# SmartHome_V3.net
KiCad netlist of a schematic drawn in Altium Designer
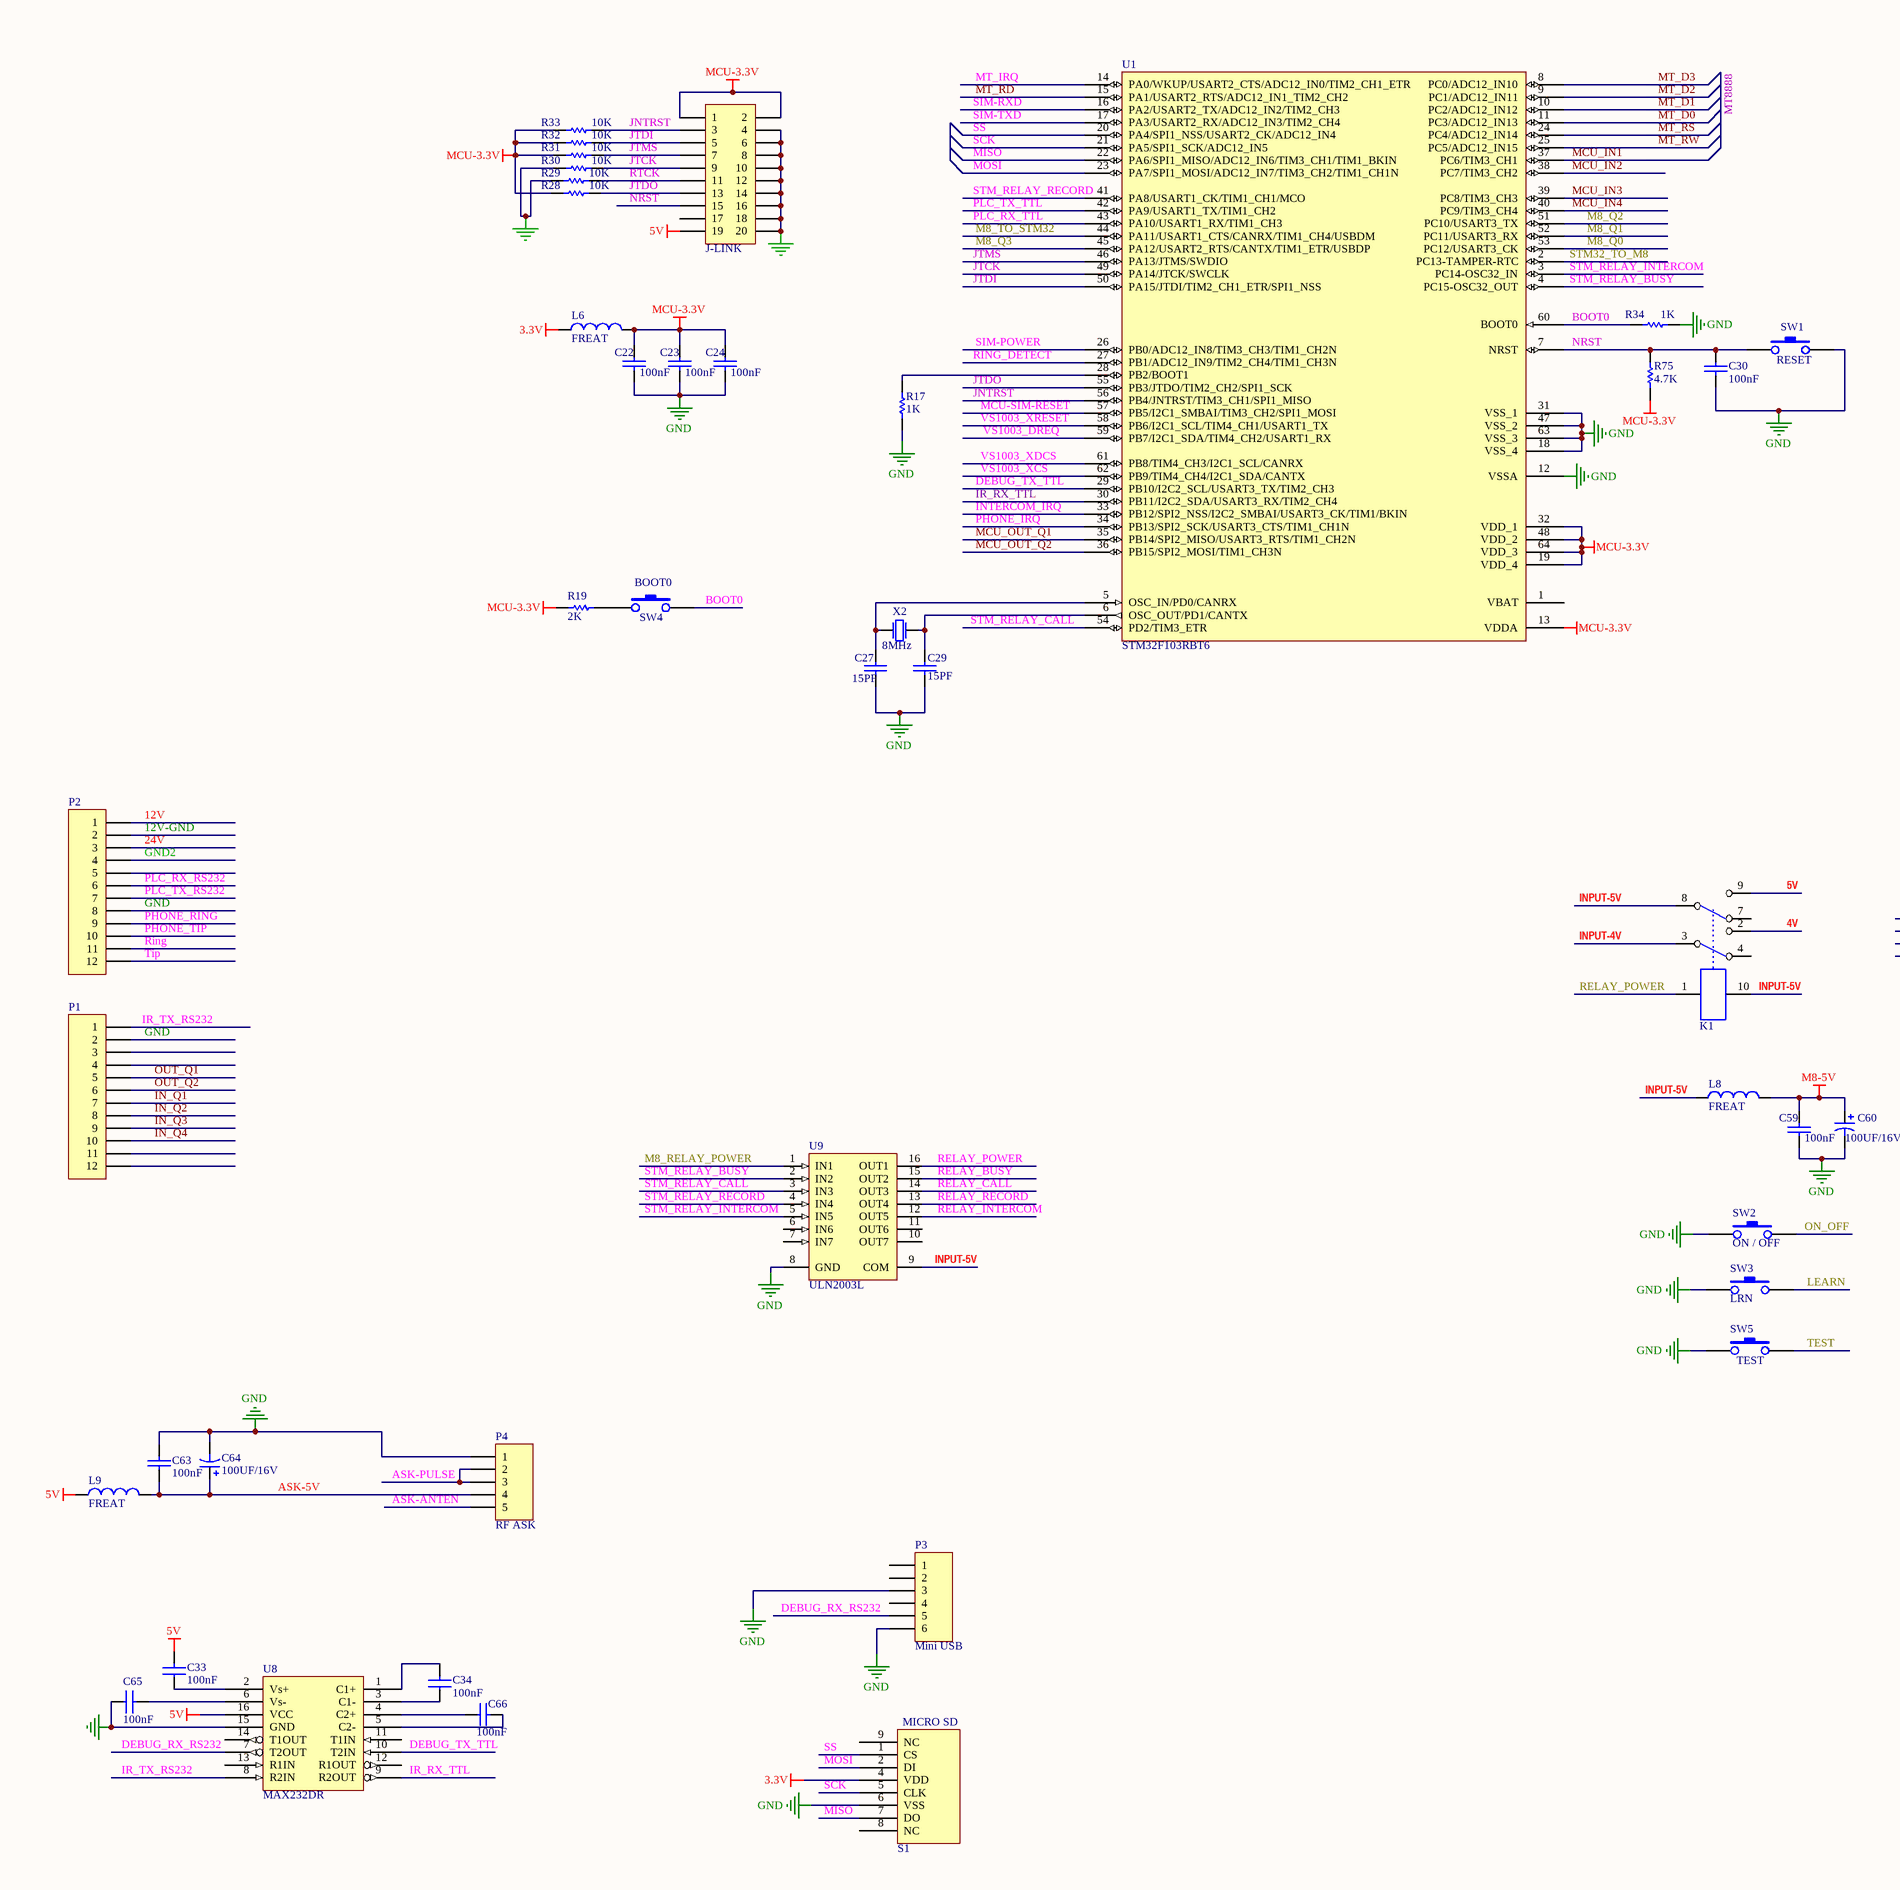
[diagram p0: SmartHome V3.SchDoc, left]
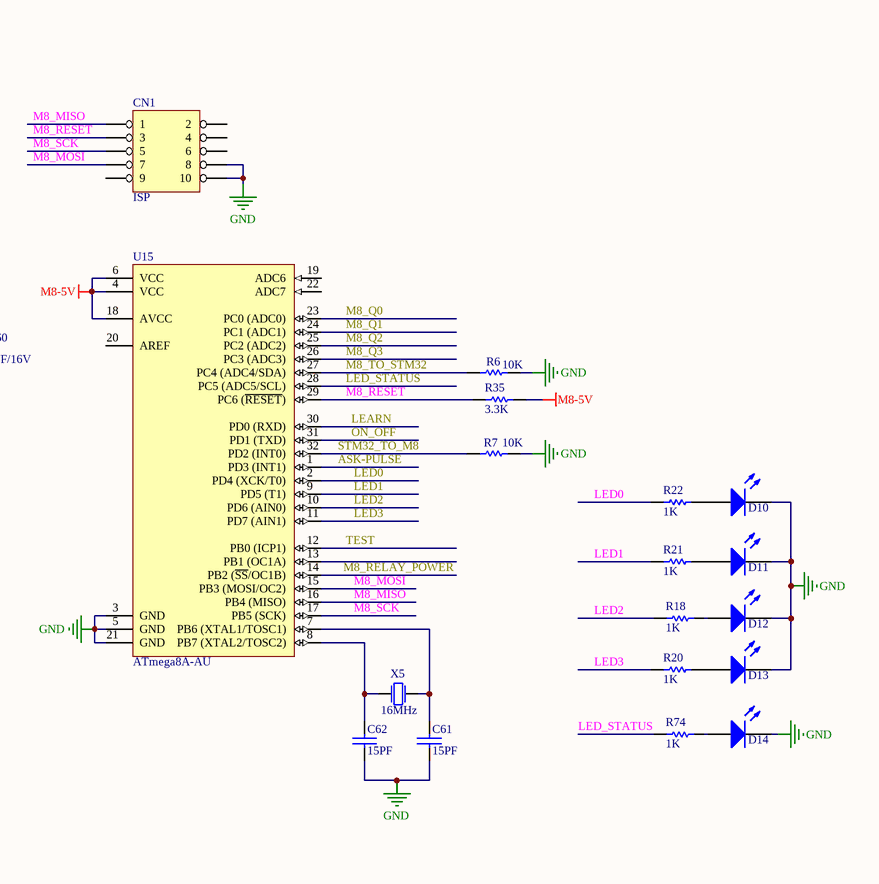
[diagram p1: SmartHome V3.SchDoc, right]

(export (version "E")
  (design (tool "Eeschema 10.0.6"))
  (components
    (comp (ref "C22") (value "100nF") (footprint "0805C") (libsource (lib "*") (part "CAP")))
    (comp (ref "C23") (value "100nF") (footprint "0805C") (libsource (lib "*") (part "CAP")))
    (comp (ref "C24") (value "100nF") (footprint "0805C") (libsource (lib "*") (part "CAP")))
    (comp (ref "C27")
      (value "15PF")
      (footprint "0805c")
      (description "Capacitor")
      (libsource (lib "") (part "CAP_1"))
    )
    (comp (ref "C29")
      (value "15PF")
      (footprint "0805c")
      (description "Capacitor")
      (libsource (lib "") (part "CAP_1"))
    )
    (comp (ref "C30")
      (value "100nF")
      (footprint "0805C")
      (description "Capacitor")
      (libsource (lib "") (part "CAP_1"))
    )
    (comp (ref "C33") (value "100nF") (footprint "0805C") (libsource (lib "*") (part "CAP NP")))
    (comp (ref "C34") (value "100nF") (footprint "0805c") (libsource (lib "*") (part "CAP NP")))
    (comp (ref "C59") (value "100nF") (footprint "0805C") (libsource (lib "*") (part "CAP")))
    (comp (ref "C60")
      (value "100UF/16V")
      (footprint "100UF-SMD")
      (description "Polarized Capacitor (Radial)")
      (fields (field (name "Comment") "100uF / 16V SMD"))
      (libsource (lib "Miscellaneous Devices") (part "Cap Pol1"))
    )
    (comp (ref "C61")
      (value "15PF")
      (footprint "0805c")
      (description "Capacitor")
      (libsource (lib "") (part "CAP_1"))
    )
    (comp (ref "C62")
      (value "15PF")
      (footprint "0805c")
      (description "Capacitor")
      (libsource (lib "") (part "CAP_1"))
    )
    (comp (ref "C63") (value "100nF") (footprint "0805C") (libsource (lib "*") (part "CAP")))
    (comp (ref "C64")
      (value "100UF/16V")
      (footprint "100UF-SMD")
      (description "Polarized Capacitor (Radial)")
      (fields (field (name "Comment") "100uF / 16V SMD"))
      (libsource (lib "") (part "Cap Pol1_1"))
    )
    (comp (ref "C65") (value "100nF") (footprint "0805c") (libsource (lib "*") (part "CAP NP")))
    (comp (ref "C66") (value "100nF") (footprint "0805c") (libsource (lib "*") (part "CAP NP")))
    (comp (ref "CN1") (value "ISP") (footprint "IDC2.54-V10D") (libsource (lib "*") (part "HEADER 5X2")))
    (comp (ref "D10")
      (value "LED")
      (footprint "0805D")
      (description "Typical BLUE SiC LED")
      (fields (field (name "PUBLISHER") "Altium Limited"))
      (libsource (lib "Miscellaneous Devices") (part "LED3"))
    )
    (comp (ref "D11")
      (value "LED")
      (footprint "0805D")
      (description "Typical BLUE SiC LED")
      (fields (field (name "PUBLISHER") "Altium Limited"))
      (libsource (lib "Miscellaneous Devices") (part "LED3"))
    )
    (comp (ref "D12")
      (value "LED")
      (footprint "0805D")
      (description "Typical BLUE SiC LED")
      (fields (field (name "PUBLISHER") "Altium Limited"))
      (libsource (lib "Miscellaneous Devices") (part "LED3"))
    )
    (comp (ref "D13")
      (value "LED")
      (footprint "0805D")
      (description "Typical BLUE SiC LED")
      (fields (field (name "PUBLISHER") "Altium Limited"))
      (libsource (lib "Miscellaneous Devices") (part "LED3"))
    )
    (comp (ref "D14")
      (value "LED")
      (footprint "0805D")
      (description "Typical BLUE SiC LED")
      (fields (field (name "PUBLISHER") "Altium Limited"))
      (libsource (lib "Miscellaneous Devices") (part "LED3"))
    )
    (comp (ref "J-LINK")
      (value "IDC 20")
      (footprint "IDC2.54-V20D")
      (description "Header, 10-Pin, Dual row")
      (fields (field (name "PUBLISHER") "Altium Limited"))
      (libsource (lib "*") (part "Header 10X2"))
    )
    (comp (ref "K1")
      (value "RELAY 5V")
      (footprint "RELAY G6H")
      (libsource (lib "*") (part "RELAY DPDT-G6HU"))
    )
    (comp (ref "L6")
      (value "FREAT")
      (footprint "1206")
      (description "Inductor")
      (fields (field (name "PUBLISHER") "Altium Limited"))
      (libsource (lib "Miscellaneous Devices") (part "Inductor"))
    )
    (comp (ref "L8")
      (value "FREAT")
      (footprint "1206")
      (description "Inductor")
      (fields (field (name "PUBLISHER") "Altium Limited"))
      (libsource (lib "Miscellaneous Devices") (part "Inductor"))
    )
    (comp (ref "L9")
      (value "FREAT")
      (footprint "1206")
      (description "Inductor")
      (fields (field (name "PUBLISHER") "Altium Limited"))
      (libsource (lib "") (part "Inductor_1"))
    )
    (comp (ref "P1")
      (value "FONIX-12")
      (footprint "Fonit_Conector")
      (description "Header, 12-Pin")
      (fields (field (name "PUBLISHER") "Altium Limited"))
      (libsource (lib "Miscellaneous Connectors") (part "Header 12"))
    )
    (comp (ref "P2")
      (value "FONIX-12")
      (footprint "Fonit_Conector")
      (description "Header, 12-Pin")
      (fields (field (name "PUBLISHER") "Altium Limited"))
      (libsource (lib "Miscellaneous Connectors") (part "Header 12"))
    )
    (comp (ref "P3")
      (value "Mini USB")
      (footprint "miniusb")
      (description "Header, 5-Pin")
      (fields (field (name "PUBLISHER") "DEBUGGER"))
      (libsource (lib "SmartHome V3") (part "Header 5"))
    )
    (comp (ref "P4")
      (value "RF ASK")
      (footprint "ASK-RF")
      (description "Header, 5-Pin")
      (fields (field (name "PUBLISHER") "Altium Limited"))
      (libsource (lib "Miscellaneous Connectors") (part "Header 5"))
    )
    (comp (ref "R6")
      (value "10K")
      (footprint "0805")
      (description "Semiconductor Resistor")
      (fields (field (name "PUBLISHER") "Altium Limited"))
      (libsource (lib "Miscellaneous Devices") (part "Res Semi"))
    )
    (comp (ref "R7")
      (value "10K")
      (footprint "0805")
      (description "Semiconductor Resistor")
      (fields (field (name "PUBLISHER") "Altium Limited"))
      (libsource (lib "Miscellaneous Devices") (part "Res Semi"))
    )
    (comp (ref "R17")
      (value "1K")
      (footprint "0805")
      (description "Semiconductor Resistor")
      (fields (field (name "Comment") "10K") (field (name "PUBLISHER") "Altium Limited"))
      (libsource (lib "Miscellaneous Devices") (part "Res Semi"))
    )
    (comp (ref "R18")
      (value "1K")
      (footprint "0805")
      (description "Resistor")
      (fields (field (name "PUBLISHER") "Altium Limited"))
      (libsource (lib "*") (part "Res1"))
    )
    (comp (ref "R19")
      (value "2K")
      (footprint "0805")
      (description "Semiconductor Resistor")
      (fields (field (name "Comment") "10K") (field (name "PUBLISHER") "Altium Limited"))
      (libsource (lib "Miscellaneous Devices") (part "Res Semi"))
    )
    (comp (ref "R20")
      (value "1K")
      (footprint "0805")
      (description "Resistor")
      (fields (field (name "PUBLISHER") "Altium Limited"))
      (libsource (lib "*") (part "Res1"))
    )
    (comp (ref "R21")
      (value "1K")
      (footprint "0805")
      (description "Resistor")
      (fields (field (name "PUBLISHER") "Altium Limited"))
      (libsource (lib "*") (part "Res1"))
    )
    (comp (ref "R22")
      (value "1K")
      (footprint "0805")
      (description "Resistor")
      (fields (field (name "PUBLISHER") "Altium Limited"))
      (libsource (lib "*") (part "Res1"))
    )
    (comp (ref "R28")
      (value "10K")
      (footprint "0805")
      (description "Resistor")
      (fields (field (name "PUBLISHER") "Altium Limited"))
      (libsource (lib "*") (part "Res1"))
    )
    (comp (ref "R29")
      (value "10K")
      (footprint "0805")
      (description "Resistor")
      (fields (field (name "PUBLISHER") "Altium Limited"))
      (libsource (lib "*") (part "Res1"))
    )
    (comp (ref "R30")
      (value "10K")
      (footprint "0805")
      (description "Resistor")
      (fields (field (name "PUBLISHER") "Altium Limited"))
      (libsource (lib "*") (part "Res1"))
    )
    (comp (ref "R31")
      (value "10K")
      (footprint "0805")
      (description "Resistor")
      (fields (field (name "PUBLISHER") "Altium Limited"))
      (libsource (lib "*") (part "Res1"))
    )
    (comp (ref "R32")
      (value "10K")
      (footprint "0805")
      (description "Resistor")
      (fields (field (name "PUBLISHER") "Altium Limited"))
      (libsource (lib "*") (part "Res1"))
    )
    (comp (ref "R33")
      (value "10K")
      (footprint "0805")
      (description "Resistor")
      (fields (field (name "PUBLISHER") "Altium Limited"))
      (libsource (lib "*") (part "Res1"))
    )
    (comp (ref "R34")
      (value "1K")
      (footprint "0805")
      (description "Semiconductor Resistor")
      (fields (field (name "PUBLISHER") "Altium Limited"))
      (libsource (lib "Miscellaneous Devices") (part "Res Semi"))
    )
    (comp (ref "R35")
      (value "3.3K")
      (footprint "0805")
      (description "Semiconductor Resistor")
      (fields (field (name "PUBLISHER") "Altium Limited"))
      (libsource (lib "Miscellaneous Devices") (part "Res Semi"))
    )
    (comp (ref "R74")
      (value "1K")
      (footprint "0805")
      (description "Resistor")
      (fields (field (name "PUBLISHER") "Altium Limited"))
      (libsource (lib "*") (part "Res1"))
    )
    (comp (ref "R75")
      (value "4.7K")
      (footprint "0805")
      (description "Semiconductor Resistor")
      (fields (field (name "PUBLISHER") "Altium Limited"))
      (libsource (lib "Miscellaneous Devices") (part "Res Semi"))
    )
    (comp (ref "S1")
      (value "MICRO SD")
      (footprint "MicroSD")
      (libsource (lib "Sheet1") (part "Component_1_1"))
    )
    (comp (ref "SW1")
      (value "SWITCH")
      (footprint "SWICH")
      (fields (field (name "ALTIUM_UNNAMED_2") "RESET"))
      (libsource (lib "*") (part "SW-PB"))
    )
    (comp (ref "SW2")
      (value "SWITCH")
      (footprint "SWICH")
      (fields (field (name "ALTIUM_UNNAMED_2") "ON / OFF"))
      (libsource (lib "*") (part "SW-PB"))
    )
    (comp (ref "SW3")
      (value "SWITCH")
      (footprint "SWICH")
      (fields (field (name "ALTIUM_UNNAMED_2") "LRN"))
      (libsource (lib "*") (part "SW-PB"))
    )
    (comp (ref "SW4")
      (value "SWITCH")
      (footprint "SWICH")
      (fields (field (name "ALTIUM_UNNAMED_1") "BOOT0"))
      (libsource (lib "*") (part "SW-PB"))
    )
    (comp (ref "SW5")
      (value "SWITCH")
      (footprint "SWICH")
      (fields (field (name "ALTIUM_UNNAMED_2") "TEST"))
      (libsource (lib "*") (part "SW-PB"))
    )
    (comp (ref "U1")
      (value "STM32F103RBT6")
      (footprint "LQFP64_L")
      (description "STM32 ARM-based 32-bit MCU with 128 Kbytes Flash, 64-pin LQFP, Industrial Temperature")
      (fields (field (name "PUBLISHER") "Altium Limited"))
      (libsource (lib "HomeAutomation") (part "STM32F103RBT6"))
    )
    (comp (ref "U8")
      (value "MAX232DR")
      (footprint "L16_N")
      (description "DUAL EIA-232 DRIVER/RECEIVER")
      (libsource (lib "*") (part "MAX232"))
    )
    (comp (ref "U9")
      (value "ULN2003L")
      (footprint "L16_N")
      (description "High-Voltage, High-Current Darlington Array")
      (fields (field (name "PUBLISHER") "Altium Limited"))
      (libsource (lib "Allegro Interface Darlington Driver") (part "ULN2003L"))
    )
    (comp (ref "U15")
      (value "ATmega8A-AU")
      (footprint "32A_N")
      (fields (field (name "PUBLISHER") "Altium Limited"))
      (libsource (lib "Atmel Microcontroller 8-Bit megaAVR") (part "ATmega8A-AU"))
    )
    (comp (ref "X2")
      (value "8MHz")
      (footprint "crystal")
      (description "Crystal Oscillator")
      (libsource (lib "*") (part "16.000MHZ"))
    )
    (comp (ref "X5")
      (value "16MHz")
      (footprint "crystal")
      (description "Crystal Oscillator")
      (libsource (lib "*") (part "16.000MHZ"))
    )
  )
  (nets
    (net (code "2") (name "/4V") (class "Default")
      (node (ref "K1") (pin "2") (pinfunction "NO1_2") (pintype "passive"))
    )
    (net (code "3") (name "/12V") (class "Default")
      (node (ref "P2") (pin "1") (pinfunction "1_1") (pintype "passive"))
    )
    (net (code "4") (name "/12V-GND") (class "Default")
      (node (ref "P2") (pin "2") (pinfunction "2_2") (pintype "passive"))
    )
    (net (code "5") (name "/24V") (class "Default")
      (node (ref "P2") (pin "3") (pinfunction "3_3") (pintype "passive"))
    )
    (net (code "6") (name "/ASK-5V") (class "Default")
      (node (ref "C63") (pin "1") (pintype "passive"))
      (node (ref "C64") (pin "1") (pinfunction "1_1") (pintype "passive"))
      (node (ref "L9") (pin "2") (pinfunction "2_2") (pintype "passive"))
      (node (ref "P4") (pin "4") (pinfunction "4_4") (pintype "passive"))
    )
    (net (code "7") (name "/ASK-ANTEN") (class "Default")
      (node (ref "P4") (pin "5") (pinfunction "5_5") (pintype "passive"))
    )
    (net (code "8") (name "/ASK-PULSE") (class "Default")
      (node (ref "P4") (pin "2") (pinfunction "2_2") (pintype "passive"))
      (node (ref "P4") (pin "3") (pinfunction "3_3") (pintype "passive"))
      (node (ref "U15") (pin "1") (pinfunction "PD3_(INT1)_1") (pintype "bidirectional"))
    )
    (net (code "9") (name "/BOOT0") (class "Default")
      (node (ref "R34") (pin "1") (pinfunction "1_1") (pintype "passive"))
      (node (ref "SW4") (pin "1") (pinfunction "1_1") (pintype "passive"))
      (node (ref "U1") (pin "60") (pinfunction "BOOT0_60") (pintype "input"))
    )
    (net (code "10") (name "/DEBUG_RX_RS232") (class "Default")
      (node (ref "P3") (pin "5") (pinfunction "5_5") (pintype "passive"))
      (node (ref "U8") (pin "7") (pinfunction "T2OUT_7") (pintype "output"))
    )
    (net (code "11") (name "/DEBUG_TX_TTL") (class "Default")
      (node (ref "U1") (pin "29") (pinfunction "PB10/I2C2_SCL/USART3_TX/TIM2_CH3_29") (pintype "bidirectional"))
      (node (ref "U8") (pin "10") (pinfunction "T2IN_10") (pintype "input"))
    )
    (net (code "12") (name "/GND2") (class "Default")
      (node (ref "P2") (pin "4") (pinfunction "4_4") (pintype "passive"))
    )
    (net (code "13") (name "/INPUT-4V") (class "Default")
      (node (ref "K1") (pin "3") (pinfunction "C1_3") (pintype "passive"))
    )
    (net (code "14") (name "/INPUT-5V") (class "Default")
      (node (ref "K1") (pin "10") (pinfunction "-_10") (pintype "passive"))
      (node (ref "K1") (pin "8") (pinfunction "C2_8") (pintype "passive"))
      (node (ref "L8") (pin "2") (pinfunction "2_2") (pintype "passive"))
      (node (ref "U9") (pin "9") (pinfunction "COM_9") (pintype "passive"))
    )
    (net (code "15") (name "/INTERCOM_IRQ") (class "Default")
      (node (ref "U1") (pin "33") (pinfunction "PB12/SPI2_NSS/I2C2_SMBAI/USART3_CK/TIM1/BKIN_33") (pintype "bidirectional"))
    )
    (net (code "16") (name "/IN_Q1") (class "Default")
      (node (ref "P1") (pin "7") (pinfunction "7_7") (pintype "passive"))
    )
    (net (code "17") (name "/IN_Q2") (class "Default")
      (node (ref "P1") (pin "8") (pinfunction "8_8") (pintype "passive"))
    )
    (net (code "18") (name "/IN_Q3") (class "Default")
      (node (ref "P1") (pin "9") (pinfunction "9_9") (pintype "passive"))
    )
    (net (code "19") (name "/IN_Q4") (class "Default")
      (node (ref "P1") (pin "10") (pinfunction "10_10") (pintype "passive"))
    )
    (net (code "20") (name "/IR_RX_TTL") (class "Default")
      (node (ref "U1") (pin "30") (pinfunction "PB11/I2C2_SDA/USART3_RX/TIM2_CH4_30") (pintype "bidirectional"))
      (node (ref "U8") (pin "9") (pinfunction "R2OUT_9") (pintype "output"))
    )
    (net (code "21") (name "/IR_TX_RS232") (class "Default")
      (node (ref "P1") (pin "1") (pinfunction "1_1") (pintype "passive"))
      (node (ref "U8") (pin "8") (pinfunction "R2IN_8") (pintype "input"))
    )
    (net (code "22") (name "/JNTRST") (class "Default")
      (node (ref "J-LINK") (pin "3") (pinfunction "3_3") (pintype "passive"))
      (node (ref "R33") (pin "1") (pinfunction "1_1") (pintype "passive"))
      (node (ref "U1") (pin "56") (pinfunction "PB4/JNTRST/TIM3_CH1/SPI1_MISO_56") (pintype "bidirectional"))
    )
    (net (code "23") (name "/JTCK") (class "Default")
      (node (ref "J-LINK") (pin "9") (pinfunction "9_9") (pintype "passive"))
      (node (ref "R30") (pin "1") (pinfunction "1_1") (pintype "passive"))
      (node (ref "U1") (pin "49") (pinfunction "PA14/JTCK/SWCLK_49") (pintype "bidirectional"))
    )
    (net (code "24") (name "/JTDI") (class "Default")
      (node (ref "J-LINK") (pin "5") (pinfunction "5_5") (pintype "passive"))
      (node (ref "R32") (pin "1") (pinfunction "1_1") (pintype "passive"))
      (node (ref "U1") (pin "50") (pinfunction "PA15/JTDI/TIM2_CH1_ETR/SPI1_NSS_50") (pintype "bidirectional"))
    )
    (net (code "25") (name "/JTDO") (class "Default")
      (node (ref "J-LINK") (pin "13") (pinfunction "13_13") (pintype "passive"))
      (node (ref "R28") (pin "1") (pinfunction "1_1") (pintype "passive"))
      (node (ref "U1") (pin "55") (pinfunction "PB3/JTDO/TIM2_CH2/SPI1_SCK_55") (pintype "bidirectional"))
    )
    (net (code "26") (name "/JTMS") (class "Default")
      (node (ref "J-LINK") (pin "7") (pinfunction "7_7") (pintype "passive"))
      (node (ref "R31") (pin "1") (pinfunction "1_1") (pintype "passive"))
      (node (ref "U1") (pin "46") (pinfunction "PA13/JTMS/SWDIO_46") (pintype "bidirectional"))
    )
    (net (code "27") (name "/LEARN") (class "Default")
      (node (ref "SW3") (pin "1") (pinfunction "1_1") (pintype "passive"))
      (node (ref "U15") (pin "30") (pinfunction "PD0_(RXD)_30") (pintype "bidirectional"))
    )
    (net (code "28") (name "/LED0") (class "Default")
      (node (ref "R22") (pin "1") (pinfunction "1_1") (pintype "passive"))
      (node (ref "U15") (pin "2") (pinfunction "PD4_(XCK/T0)_2") (pintype "bidirectional"))
    )
    (net (code "29") (name "/LED1") (class "Default")
      (node (ref "R21") (pin "1") (pinfunction "1_1") (pintype "passive"))
      (node (ref "U15") (pin "9") (pinfunction "PD5_(T1)_9") (pintype "bidirectional"))
    )
    (net (code "30") (name "/LED2") (class "Default")
      (node (ref "R18") (pin "1") (pinfunction "1_1") (pintype "passive"))
      (node (ref "U15") (pin "10") (pinfunction "PD6_(AIN0)_10") (pintype "bidirectional"))
    )
    (net (code "31") (name "/LED3") (class "Default")
      (node (ref "R20") (pin "1") (pinfunction "1_1") (pintype "passive"))
      (node (ref "U15") (pin "11") (pinfunction "PD7_(AIN1)_11") (pintype "bidirectional"))
    )
    (net (code "32") (name "/LED_STATUS") (class "Default")
      (node (ref "R74") (pin "1") (pinfunction "1_1") (pintype "passive"))
      (node (ref "U15") (pin "28") (pinfunction "PC5_(ADC5/SCL)_28") (pintype "bidirectional"))
    )
    (net (code "33") (name "/M8_MISO") (class "Default")
      (node (ref "CN1") (pin "1") (pinfunction "1_1") (pintype "passive"))
      (node (ref "U15") (pin "16") (pinfunction "PB4_(MISO)_16") (pintype "bidirectional"))
    )
    (net (code "34") (name "/M8_MOSI") (class "Default")
      (node (ref "CN1") (pin "7") (pinfunction "7_7") (pintype "passive"))
      (node (ref "U15") (pin "15") (pinfunction "PB3_(MOSI/OC2)_15") (pintype "bidirectional"))
    )
    (net (code "35") (name "/M8_Q0") (class "Default")
      (node (ref "U1") (pin "53") (pinfunction "PC12/USART3_CK_53") (pintype "bidirectional"))
      (node (ref "U15") (pin "23") (pinfunction "PC0_(ADC0)_23") (pintype "bidirectional"))
    )
    (net (code "36") (name "/M8_Q1") (class "Default")
      (node (ref "U1") (pin "52") (pinfunction "PC11/USART3_RX_52") (pintype "bidirectional"))
      (node (ref "U15") (pin "24") (pinfunction "PC1_(ADC1)_24") (pintype "bidirectional"))
    )
    (net (code "37") (name "/M8_Q2") (class "Default")
      (node (ref "U1") (pin "51") (pinfunction "PC10/USART3_TX_51") (pintype "bidirectional"))
      (node (ref "U15") (pin "25") (pinfunction "PC2_(ADC2)_25") (pintype "bidirectional"))
    )
    (net (code "38") (name "/M8_Q3") (class "Default")
      (node (ref "U1") (pin "45") (pinfunction "PA12/USART2_RTS/CANTX/TIM1_ETR/USBDP_45") (pintype "bidirectional"))
      (node (ref "U15") (pin "26") (pinfunction "PC3_(ADC3)_26") (pintype "bidirectional"))
    )
    (net (code "39") (name "/M8_RELAY_POWER") (class "Default")
      (node (ref "U15") (pin "14") (pinfunction "PB2_(~{SS}/OC1B)_14") (pintype "bidirectional"))
      (node (ref "U9") (pin "1") (pinfunction "IN1_1") (pintype "input"))
    )
    (net (code "40") (name "/M8_RESET") (class "Default")
      (node (ref "CN1") (pin "3") (pinfunction "3_3") (pintype "passive"))
      (node (ref "R35") (pin "1") (pinfunction "1_1") (pintype "passive"))
      (node (ref "U15") (pin "29") (pinfunction "PC6_(~{RESET})_29") (pintype "bidirectional"))
    )
    (net (code "41") (name "/M8_SCK") (class "Default")
      (node (ref "CN1") (pin "5") (pinfunction "5_5") (pintype "passive"))
      (node (ref "U15") (pin "17") (pinfunction "PB5_(SCK)_17") (pintype "bidirectional"))
    )
    (net (code "42") (name "/M8_TO_STM32") (class "Default")
      (node (ref "R6") (pin "1") (pinfunction "1_1") (pintype "passive"))
      (node (ref "U1") (pin "44") (pinfunction "PA11/USART1_CTS/CANRX/TIM1_CH4/USBDM_44") (pintype "bidirectional"))
      (node (ref "U15") (pin "27") (pinfunction "PC4_(ADC4/SDA)_27") (pintype "bidirectional"))
    )
    (net (code "43") (name "/MCU-SIM-RESET") (class "Default")
      (node (ref "U1") (pin "57") (pinfunction "PB5/I2C1_SMBAI/TIM3_CH2/SPI1_MOSI_57") (pintype "bidirectional"))
    )
    (net (code "44") (name "/MCU_IN1") (class "Default")
      (node (ref "U1") (pin "37") (pinfunction "PC6/TIM3_CH1_37") (pintype "bidirectional"))
    )
    (net (code "45") (name "/MCU_IN2") (class "Default")
      (node (ref "U1") (pin "38") (pinfunction "PC7/TIM3_CH2_38") (pintype "bidirectional"))
    )
    (net (code "46") (name "/MCU_IN3") (class "Default")
      (node (ref "U1") (pin "39") (pinfunction "PC8/TIM3_CH3_39") (pintype "bidirectional"))
    )
    (net (code "47") (name "/MCU_IN4") (class "Default")
      (node (ref "U1") (pin "40") (pinfunction "PC9/TIM3_CH4_40") (pintype "bidirectional"))
    )
    (net (code "48") (name "/MCU_OUT_Q1") (class "Default")
      (node (ref "U1") (pin "35") (pinfunction "PB14/SPI2_MISO/USART3_RTS/TIM1_CH2N_35") (pintype "bidirectional"))
    )
    (net (code "49") (name "/MCU_OUT_Q2") (class "Default")
      (node (ref "U1") (pin "36") (pinfunction "PB15/SPI2_MOSI/TIM1_CH3N_36") (pintype "bidirectional"))
    )
    (net (code "50") (name "/MISO") (class "Default")
      (node (ref "S1") (pin "7") (pinfunction "DO_7") (pintype "passive"))
      (node (ref "U1") (pin "22") (pinfunction "PA6/SPI1_MISO/ADC12_IN6/TIM3_CH1/TIM1_BKIN_22") (pintype "bidirectional"))
    )
    (net (code "51") (name "/MOSI") (class "Default")
      (node (ref "S1") (pin "2") (pinfunction "DI_2") (pintype "passive"))
      (node (ref "U1") (pin "23") (pinfunction "PA7/SPI1_MOSI/ADC12_IN7/TIM3_CH2/TIM1_CH1N_23") (pintype "bidirectional"))
    )
    (net (code "52") (name "/MT_D0") (class "Default")
      (node (ref "U1") (pin "11") (pinfunction "PC3/ADC12_IN13_11") (pintype "bidirectional"))
    )
    (net (code "53") (name "/MT_D1") (class "Default")
      (node (ref "U1") (pin "10") (pinfunction "PC2/ADC12_IN12_10") (pintype "bidirectional"))
    )
    (net (code "54") (name "/MT_D2") (class "Default")
      (node (ref "U1") (pin "9") (pinfunction "PC1/ADC12_IN11_9") (pintype "bidirectional"))
    )
    (net (code "55") (name "/MT_D3") (class "Default")
      (node (ref "U1") (pin "8") (pinfunction "PC0/ADC12_IN10_8") (pintype "bidirectional"))
    )
    (net (code "56") (name "/MT_IRQ") (class "Default")
      (node (ref "U1") (pin "14") (pinfunction "PA0/WKUP/USART2_CTS/ADC12_IN0/TIM2_CH1_ETR_14") (pintype "bidirectional"))
    )
    (net (code "57") (name "/MT_RD") (class "Default")
      (node (ref "U1") (pin "15") (pinfunction "PA1/USART2_RTS/ADC12_IN1_TIM2_CH2_15") (pintype "bidirectional"))
    )
    (net (code "58") (name "/MT_RS") (class "Default")
      (node (ref "U1") (pin "24") (pinfunction "PC4/ADC12_IN14_24") (pintype "bidirectional"))
    )
    (net (code "59") (name "/MT_RW") (class "Default")
      (node (ref "U1") (pin "25") (pinfunction "PC5/ADC12_IN15_25") (pintype "bidirectional"))
    )
    (net (code "60") (name "/NRST") (class "Default")
      (node (ref "C30") (pin "1") (pinfunction "1_1") (pintype "passive"))
      (node (ref "J-LINK") (pin "15") (pinfunction "15_15") (pintype "passive"))
      (node (ref "R75") (pin "1") (pinfunction "1_1") (pintype "passive"))
      (node (ref "SW1") (pin "1") (pinfunction "1_1") (pintype "passive"))
      (node (ref "U1") (pin "7") (pinfunction "NRST_7") (pintype "bidirectional"))
    )
    (net (code "61") (name "/ON_OFF") (class "Default")
      (node (ref "SW2") (pin "1") (pinfunction "1_1") (pintype "passive"))
      (node (ref "U15") (pin "31") (pinfunction "PD1_(TXD)_31") (pintype "bidirectional"))
    )
    (net (code "62") (name "/OUT_Q1") (class "Default")
      (node (ref "P1") (pin "5") (pinfunction "5_5") (pintype "passive"))
    )
    (net (code "63") (name "/OUT_Q2") (class "Default")
      (node (ref "P1") (pin "6") (pinfunction "6_6") (pintype "passive"))
    )
    (net (code "64") (name "/PHONE_IRQ") (class "Default")
      (node (ref "U1") (pin "34") (pinfunction "PB13/SPI2_SCK/USART3_CTS/TIM1_CH1N_34") (pintype "bidirectional"))
    )
    (net (code "65") (name "/PHONE_RING") (class "Default")
      (node (ref "P2") (pin "9") (pinfunction "9_9") (pintype "passive"))
    )
    (net (code "66") (name "/PHONE_TIP") (class "Default")
      (node (ref "P2") (pin "10") (pinfunction "10_10") (pintype "passive"))
    )
    (net (code "67") (name "/PLC_RX_RS232") (class "Default")
      (node (ref "P2") (pin "6") (pinfunction "6_6") (pintype "passive"))
    )
    (net (code "68") (name "/PLC_RX_TTL") (class "Default")
      (node (ref "U1") (pin "43") (pinfunction "PA10/USART1_RX/TIM1_CH3_43") (pintype "bidirectional"))
    )
    (net (code "69") (name "/PLC_TX_RS232") (class "Default")
      (node (ref "P2") (pin "7") (pinfunction "7_7") (pintype "passive"))
    )
    (net (code "70") (name "/PLC_TX_TTL") (class "Default")
      (node (ref "U1") (pin "42") (pinfunction "PA9/USART1_TX/TIM1_CH2_42") (pintype "bidirectional"))
    )
    (net (code "71") (name "/RELAY_BUSY") (class "Default")
      (node (ref "U9") (pin "15") (pinfunction "OUT2_15") (pintype "open_collector"))
    )
    (net (code "72") (name "/RELAY_CALL") (class "Default")
      (node (ref "U9") (pin "14") (pinfunction "OUT3_14") (pintype "open_collector"))
    )
    (net (code "73") (name "/RELAY_INTERCOM") (class "Default")
      (node (ref "U9") (pin "12") (pinfunction "OUT5_12") (pintype "open_collector"))
    )
    (net (code "74") (name "/RELAY_POWER") (class "Default")
      (node (ref "K1") (pin "1") (pinfunction "+_1") (pintype "passive"))
      (node (ref "U9") (pin "16") (pinfunction "OUT1_16") (pintype "open_collector"))
    )
    (net (code "75") (name "/RELAY_RECORD") (class "Default")
      (node (ref "U9") (pin "13") (pinfunction "OUT4_13") (pintype "open_collector"))
    )
    (net (code "76") (name "/RING_DETECT") (class "Default")
      (node (ref "U1") (pin "27") (pinfunction "PB1/ADC12_IN9/TIM2_CH4/TIM1_CH3N_27") (pintype "bidirectional"))
    )
    (net (code "77") (name "/RTCK") (class "Default")
      (node (ref "J-LINK") (pin "11") (pinfunction "11_11") (pintype "passive"))
      (node (ref "R29") (pin "1") (pinfunction "1_1") (pintype "passive"))
    )
    (net (code "78") (name "/Ring") (class "Default")
      (node (ref "P2") (pin "11") (pinfunction "11_11") (pintype "passive"))
    )
    (net (code "79") (name "/SCK") (class "Default")
      (node (ref "S1") (pin "5") (pinfunction "CLK_5") (pintype "passive"))
      (node (ref "U1") (pin "21") (pinfunction "PA5/SPI1_SCK/ADC12_IN5_21") (pintype "bidirectional"))
    )
    (net (code "80") (name "/SIM-POWER") (class "Default")
      (node (ref "U1") (pin "26") (pinfunction "PB0/ADC12_IN8/TIM3_CH3/TIM1_CH2N_26") (pintype "bidirectional"))
    )
    (net (code "81") (name "/SIM-RXD") (class "Default")
      (node (ref "U1") (pin "16") (pinfunction "PA2/USART2_TX/ADC12_IN2/TIM2_CH3_16") (pintype "bidirectional"))
    )
    (net (code "82") (name "/SIM-TXD") (class "Default")
      (node (ref "U1") (pin "17") (pinfunction "PA3/USART2_RX/ADC12_IN3/TIM2_CH4_17") (pintype "bidirectional"))
    )
    (net (code "83") (name "/SS") (class "Default")
      (node (ref "S1") (pin "1") (pinfunction "CS_1") (pintype "passive"))
      (node (ref "U1") (pin "20") (pinfunction "PA4/SPI1_NSS/USART2_CK/ADC12_IN4_20") (pintype "bidirectional"))
    )
    (net (code "84") (name "/STM32_TO_M8") (class "Default")
      (node (ref "R7") (pin "1") (pinfunction "1_1") (pintype "passive"))
      (node (ref "U1") (pin "2") (pinfunction "PC13-TAMPER-RTC_2") (pintype "bidirectional"))
      (node (ref "U15") (pin "32") (pinfunction "PD2_(INT0)_32") (pintype "bidirectional"))
    )
    (net (code "85") (name "/STM_RELAY_BUSY") (class "Default")
      (node (ref "U1") (pin "4") (pinfunction "PC15-OSC32_OUT_4") (pintype "bidirectional"))
      (node (ref "U9") (pin "2") (pinfunction "IN2_2") (pintype "input"))
    )
    (net (code "86") (name "/STM_RELAY_CALL") (class "Default")
      (node (ref "U1") (pin "54") (pinfunction "PD2/TIM3_ETR_54") (pintype "bidirectional"))
      (node (ref "U9") (pin "3") (pinfunction "IN3_3") (pintype "input"))
    )
    (net (code "87") (name "/STM_RELAY_INTERCOM") (class "Default")
      (node (ref "U1") (pin "3") (pinfunction "PC14-OSC32_IN_3") (pintype "bidirectional"))
      (node (ref "U9") (pin "5") (pinfunction "IN5_5") (pintype "input"))
    )
    (net (code "88") (name "/STM_RELAY_RECORD") (class "Default")
      (node (ref "U1") (pin "41") (pinfunction "PA8/USART1_CK/TIM1_CH1/MCO_41") (pintype "bidirectional"))
      (node (ref "U9") (pin "4") (pinfunction "IN4_4") (pintype "input"))
    )
    (net (code "89") (name "/TEST") (class "Default")
      (node (ref "SW5") (pin "1") (pinfunction "1_1") (pintype "passive"))
      (node (ref "U15") (pin "12") (pinfunction "PB0_(ICP1)_12") (pintype "bidirectional"))
    )
    (net (code "90") (name "/Tip") (class "Default")
      (node (ref "P2") (pin "12") (pinfunction "12_12") (pintype "passive"))
    )
    (net (code "91") (name "/VS1003_DREQ") (class "Default")
      (node (ref "U1") (pin "59") (pinfunction "PB7/I2C1_SDA/TIM4_CH2/USART1_RX_59") (pintype "bidirectional"))
    )
    (net (code "92") (name "/VS1003_XCS") (class "Default")
      (node (ref "U1") (pin "62") (pinfunction "PB9/TIM4_CH4/I2C1_SDA/CANTX_62") (pintype "bidirectional"))
    )
    (net (code "93") (name "/VS1003_XDCS") (class "Default")
      (node (ref "U1") (pin "61") (pinfunction "PB8/TIM4_CH3/I2C1_SCL/CANRX_61") (pintype "bidirectional"))
    )
    (net (code "94") (name "/VS1003_XRESET") (class "Default")
      (node (ref "U1") (pin "58") (pinfunction "PB6/I2C1_SCL/TIM4_CH1/USART1_TX_58") (pintype "bidirectional"))
    )
    (net (code "96") (name "3.3V") (class "Default")
      (node (ref "L6") (pin "2") (pinfunction "2_2") (pintype "passive"))
      (node (ref "S1") (pin "4") (pinfunction "VDD_4") (pintype "passive"))
    )
    (net (code "97") (name "5V") (class "Default")
      (node (ref "C33") (pin "2") (pinfunction "2_2") (pintype "passive"))
      (node (ref "J-LINK") (pin "19") (pinfunction "19_19") (pintype "passive"))
      (node (ref "K1") (pin "9") (pinfunction "NO2_9") (pintype "passive"))
      (node (ref "L9") (pin "1") (pinfunction "1_1") (pintype "passive"))
      (node (ref "U8") (pin "16") (pinfunction "VCC_16") (pintype "power_in"))
    )
    (net (code "98") (name "GND") (class "Default")
      (node (ref "C22") (pin "2") (pintype "passive"))
      (node (ref "C23") (pin "2") (pintype "passive"))
      (node (ref "C24") (pin "2") (pintype "passive"))
      (node (ref "C27") (pin "2") (pinfunction "2_2") (pintype "passive"))
      (node (ref "C29") (pin "2") (pinfunction "2_2") (pintype "passive"))
      (node (ref "C30") (pin "2") (pinfunction "2_2") (pintype "passive"))
      (node (ref "C59") (pin "2") (pintype "passive"))
      (node (ref "C60") (pin "2") (pinfunction "2_2") (pintype "passive"))
      (node (ref "C61") (pin "2") (pinfunction "2_2") (pintype "passive"))
      (node (ref "C62") (pin "2") (pinfunction "2_2") (pintype "passive"))
      (node (ref "C63") (pin "2") (pintype "passive"))
      (node (ref "C64") (pin "2") (pinfunction "2_2") (pintype "passive"))
      (node (ref "C65") (pin "1") (pinfunction "1_1") (pintype "passive"))
      (node (ref "CN1") (pin "10") (pinfunction "10_10") (pintype "passive"))
      (node (ref "CN1") (pin "8") (pinfunction "8_8") (pintype "passive"))
      (node (ref "D10") (pin "2") (pinfunction "K_2") (pintype "passive"))
      (node (ref "D11") (pin "2") (pinfunction "K_2") (pintype "passive"))
      (node (ref "D12") (pin "2") (pinfunction "K_2") (pintype "passive"))
      (node (ref "D13") (pin "2") (pinfunction "K_2") (pintype "passive"))
      (node (ref "D14") (pin "2") (pinfunction "K_2") (pintype "passive"))
      (node (ref "J-LINK") (pin "10") (pinfunction "10_10") (pintype "passive"))
      (node (ref "J-LINK") (pin "12") (pinfunction "12_12") (pintype "passive"))
      (node (ref "J-LINK") (pin "14") (pinfunction "14_14") (pintype "passive"))
      (node (ref "J-LINK") (pin "16") (pinfunction "16_16") (pintype "passive"))
      (node (ref "J-LINK") (pin "18") (pinfunction "18_18") (pintype "passive"))
      (node (ref "J-LINK") (pin "20") (pinfunction "20_20") (pintype "passive"))
      (node (ref "J-LINK") (pin "4") (pinfunction "4_4") (pintype "passive"))
      (node (ref "J-LINK") (pin "6") (pinfunction "6_6") (pintype "passive"))
      (node (ref "J-LINK") (pin "8") (pinfunction "8_8") (pintype "passive"))
      (node (ref "P1") (pin "2") (pinfunction "2_2") (pintype "passive"))
      (node (ref "P2") (pin "8") (pinfunction "8_8") (pintype "passive"))
      (node (ref "P3") (pin "3") (pinfunction "3_3") (pintype "passive"))
      (node (ref "P3") (pin "6") (pinfunction "6_6") (pintype "passive"))
      (node (ref "P4") (pin "1") (pinfunction "1_1") (pintype "passive"))
      (node (ref "R17") (pin "1") (pinfunction "1_1") (pintype "passive"))
      (node (ref "R29") (pin "2") (pinfunction "2_2") (pintype "passive"))
      (node (ref "R30") (pin "2") (pinfunction "2_2") (pintype "passive"))
      (node (ref "R34") (pin "2") (pinfunction "2_2") (pintype "passive"))
      (node (ref "R6") (pin "2") (pinfunction "2_2") (pintype "passive"))
      (node (ref "R7") (pin "2") (pinfunction "2_2") (pintype "passive"))
      (node (ref "S1") (pin "6") (pinfunction "VSS_6") (pintype "passive"))
      (node (ref "SW1") (pin "2") (pinfunction "2_2") (pintype "passive"))
      (node (ref "SW2") (pin "2") (pinfunction "2_2") (pintype "passive"))
      (node (ref "SW3") (pin "2") (pinfunction "2_2") (pintype "passive"))
      (node (ref "SW5") (pin "2") (pinfunction "2_2") (pintype "passive"))
      (node (ref "U1") (pin "12") (pinfunction "VSSA_12") (pintype "power_in"))
      (node (ref "U1") (pin "18") (pinfunction "VSS_4_18") (pintype "power_in"))
      (node (ref "U1") (pin "31") (pinfunction "VSS_1_31") (pintype "power_in"))
      (node (ref "U1") (pin "47") (pinfunction "VSS_2_47") (pintype "power_in"))
      (node (ref "U1") (pin "63") (pinfunction "VSS_3_63") (pintype "power_in"))
      (node (ref "U15") (pin "21") (pinfunction "GND_21") (pintype "power_in"))
      (node (ref "U15") (pin "3") (pinfunction "GND_3") (pintype "power_in"))
      (node (ref "U15") (pin "5") (pinfunction "GND_5") (pintype "power_in"))
      (node (ref "U8") (pin "15") (pinfunction "GND_15") (pintype "power_in"))
      (node (ref "U9") (pin "8") (pinfunction "GND_8") (pintype "power_in"))
    )
    (net (code "99") (name "M8-5V") (class "Default")
      (node (ref "C59") (pin "1") (pintype "passive"))
      (node (ref "C60") (pin "1") (pinfunction "1_1") (pintype "passive"))
      (node (ref "L8") (pin "1") (pinfunction "1_1") (pintype "passive"))
      (node (ref "R35") (pin "2") (pinfunction "2_2") (pintype "passive"))
      (node (ref "U15") (pin "18") (pinfunction "AVCC_18") (pintype "power_in"))
      (node (ref "U15") (pin "4") (pinfunction "VCC_4") (pintype "power_in"))
      (node (ref "U15") (pin "6") (pinfunction "VCC_6") (pintype "power_in"))
    )
    (net (code "100") (name "MCU-3.3V") (class "Default")
      (node (ref "C22") (pin "1") (pintype "passive"))
      (node (ref "C23") (pin "1") (pintype "passive"))
      (node (ref "C24") (pin "1") (pintype "passive"))
      (node (ref "J-LINK") (pin "1") (pinfunction "1_1") (pintype "passive"))
      (node (ref "J-LINK") (pin "2") (pinfunction "2_2") (pintype "passive"))
      (node (ref "L6") (pin "1") (pinfunction "1_1") (pintype "passive"))
      (node (ref "R19") (pin "2") (pinfunction "2_2") (pintype "passive"))
      (node (ref "R28") (pin "2") (pinfunction "2_2") (pintype "passive"))
      (node (ref "R31") (pin "2") (pinfunction "2_2") (pintype "passive"))
      (node (ref "R32") (pin "2") (pinfunction "2_2") (pintype "passive"))
      (node (ref "R33") (pin "2") (pinfunction "2_2") (pintype "passive"))
      (node (ref "R75") (pin "2") (pinfunction "2_2") (pintype "passive"))
      (node (ref "U1") (pin "13") (pinfunction "VDDA_13") (pintype "power_in"))
      (node (ref "U1") (pin "19") (pinfunction "VDD_4_19") (pintype "power_in"))
      (node (ref "U1") (pin "32") (pinfunction "VDD_1_32") (pintype "power_in"))
      (node (ref "U1") (pin "48") (pinfunction "VDD_2_48") (pintype "power_in"))
      (node (ref "U1") (pin "64") (pinfunction "VDD_3_64") (pintype "power_in"))
    )
    (net (code "101") (name "Net-(D10-A)") (class "Default")
      (node (ref "D10") (pin "1") (pinfunction "A_1") (pintype "passive"))
      (node (ref "R22") (pin "2") (pinfunction "2_2") (pintype "passive"))
    )
    (net (code "102") (name "Net-(D11-A)") (class "Default")
      (node (ref "D11") (pin "1") (pinfunction "A_1") (pintype "passive"))
      (node (ref "R21") (pin "2") (pinfunction "2_2") (pintype "passive"))
    )
    (net (code "103") (name "Net-(D12-A)") (class "Default")
      (node (ref "D12") (pin "1") (pinfunction "A_1") (pintype "passive"))
      (node (ref "R18") (pin "2") (pinfunction "2_2") (pintype "passive"))
    )
    (net (code "104") (name "Net-(D13-A)") (class "Default")
      (node (ref "D13") (pin "1") (pinfunction "A_1") (pintype "passive"))
      (node (ref "R20") (pin "2") (pinfunction "2_2") (pintype "passive"))
    )
    (net (code "105") (name "Net-(D14-A)") (class "Default")
      (node (ref "D14") (pin "1") (pinfunction "A_1") (pintype "passive"))
      (node (ref "R74") (pin "2") (pinfunction "2_2") (pintype "passive"))
    )
    (net (code "106") (name "Net-(R19-Pad1)") (class "Default")
      (node (ref "R19") (pin "1") (pinfunction "1_1") (pintype "passive"))
      (node (ref "SW4") (pin "2") (pinfunction "2_2") (pintype "passive"))
    )
    (net (code "107") (name "Net-(U1-OSC_IN{slash}PD0{slash}CANRX)") (class "Default")
      (node (ref "C27") (pin "1") (pinfunction "1_1") (pintype "passive"))
      (node (ref "U1") (pin "5") (pinfunction "OSC_IN/PD0/CANRX_5") (pintype "input"))
      (node (ref "X2") (pin "2") (pinfunction "P2_2") (pintype "passive"))
    )
    (net (code "108") (name "Net-(U1-OSC_OUT{slash}PD1{slash}CANTX)") (class "Default")
      (node (ref "C29") (pin "1") (pinfunction "1_1") (pintype "passive"))
      (node (ref "U1") (pin "6") (pinfunction "OSC_OUT/PD1/CANTX_6") (pintype "output"))
      (node (ref "X2") (pin "1") (pinfunction "P1_1") (pintype "passive"))
    )
    (net (code "109") (name "Net-(U1-PB2{slash}BOOT1)") (class "Default")
      (node (ref "R17") (pin "2") (pinfunction "2_2") (pintype "passive"))
      (node (ref "U1") (pin "28") (pinfunction "PB2/BOOT1_28") (pintype "bidirectional"))
    )
    (net (code "110") (name "Net-(U8-C1+)") (class "Default")
      (node (ref "C34") (pin "2") (pinfunction "2_2") (pintype "passive"))
      (node (ref "U8") (pin "1") (pinfunction "C1+_1") (pintype "passive"))
    )
    (net (code "111") (name "Net-(U8-C1-)") (class "Default")
      (node (ref "C34") (pin "1") (pinfunction "1_1") (pintype "passive"))
      (node (ref "U8") (pin "3") (pinfunction "C1-_3") (pintype "passive"))
    )
    (net (code "112") (name "Net-(U8-C2+)") (class "Default")
      (node (ref "C66") (pin "1") (pinfunction "1_1") (pintype "passive"))
      (node (ref "U8") (pin "4") (pinfunction "C2+_4") (pintype "passive"))
    )
    (net (code "113") (name "Net-(U8-C2-)") (class "Default")
      (node (ref "C66") (pin "2") (pinfunction "2_2") (pintype "passive"))
      (node (ref "U8") (pin "5") (pinfunction "C2-_5") (pintype "passive"))
    )
    (net (code "114") (name "Net-(U8-Vs+)") (class "Default")
      (node (ref "C33") (pin "1") (pinfunction "1_1") (pintype "passive"))
      (node (ref "U8") (pin "2") (pinfunction "Vs+_2") (pintype "passive"))
    )
    (net (code "115") (name "Net-(U8-Vs-)") (class "Default")
      (node (ref "C65") (pin "2") (pinfunction "2_2") (pintype "passive"))
      (node (ref "U8") (pin "6") (pinfunction "Vs-_6") (pintype "passive"))
    )
    (net (code "116") (name "Net-(U15-PB6_(XTAL1{slash}TOSC1))") (class "Default")
      (node (ref "C61") (pin "1") (pinfunction "1_1") (pintype "passive"))
      (node (ref "U15") (pin "7") (pinfunction "PB6_(XTAL1/TOSC1)_7") (pintype "bidirectional"))
      (node (ref "X5") (pin "1") (pinfunction "P1_1") (pintype "passive"))
    )
    (net (code "117") (name "Net-(U15-PB7_(XTAL2{slash}TOSC2))") (class "Default")
      (node (ref "C62") (pin "1") (pinfunction "1_1") (pintype "passive"))
      (node (ref "U15") (pin "8") (pinfunction "PB7_(XTAL2/TOSC2)_8") (pintype "bidirectional"))
      (node (ref "X5") (pin "2") (pinfunction "P2_2") (pintype "passive"))
    )
    (net (code "118") (name "unconnected-(CN1-Pad2)") (class "Default")
      (node (ref "CN1") (pin "2") (pinfunction "2_2") (pintype "passive"))
    )
    (net (code "119") (name "unconnected-(CN1-Pad4)") (class "Default")
      (node (ref "CN1") (pin "4") (pinfunction "4_4") (pintype "passive"))
    )
    (net (code "120") (name "unconnected-(CN1-Pad6)") (class "Default")
      (node (ref "CN1") (pin "6") (pinfunction "6_6") (pintype "passive"))
    )
    (net (code "121") (name "unconnected-(CN1-Pad9)") (class "Default")
      (node (ref "CN1") (pin "9") (pinfunction "9_9") (pintype "passive"))
    )
    (net (code "122") (name "unconnected-(J-LINK-Pad17)") (class "Default")
      (node (ref "J-LINK") (pin "17") (pinfunction "17_17") (pintype "passive"))
    )
    (net (code "123") (name "unconnected-(K1-NC1-Pad4)") (class "Default")
      (node (ref "K1") (pin "4") (pinfunction "NC1_4") (pintype "passive"))
    )
    (net (code "124") (name "unconnected-(K1-NC2-Pad7)") (class "Default")
      (node (ref "K1") (pin "7") (pinfunction "NC2_7") (pintype "passive"))
    )
    (net (code "125") (name "unconnected-(P1-Pad3)") (class "Default")
      (node (ref "P1") (pin "3") (pinfunction "3_3") (pintype "passive"))
    )
    (net (code "126") (name "unconnected-(P1-Pad4)") (class "Default")
      (node (ref "P1") (pin "4") (pinfunction "4_4") (pintype "passive"))
    )
    (net (code "127") (name "unconnected-(P1-Pad11)") (class "Default")
      (node (ref "P1") (pin "11") (pinfunction "11_11") (pintype "passive"))
    )
    (net (code "128") (name "unconnected-(P1-Pad12)") (class "Default")
      (node (ref "P1") (pin "12") (pinfunction "12_12") (pintype "passive"))
    )
    (net (code "129") (name "unconnected-(P2-Pad5)") (class "Default")
      (node (ref "P2") (pin "5") (pinfunction "5_5") (pintype "passive"))
    )
    (net (code "130") (name "unconnected-(P3-Pad1)") (class "Default")
      (node (ref "P3") (pin "1") (pinfunction "1_1") (pintype "passive"))
    )
    (net (code "131") (name "unconnected-(P3-Pad2)") (class "Default")
      (node (ref "P3") (pin "2") (pinfunction "2_2") (pintype "passive"))
    )
    (net (code "132") (name "unconnected-(P3-Pad4)") (class "Default")
      (node (ref "P3") (pin "4") (pinfunction "4_4") (pintype "passive"))
    )
    (net (code "133") (name "unconnected-(S1-NC-Pad8)") (class "Default")
      (node (ref "S1") (pin "8") (pinfunction "NC_8") (pintype "passive"))
    )
    (net (code "134") (name "unconnected-(S1-NC-Pad9)") (class "Default")
      (node (ref "S1") (pin "9") (pinfunction "NC_9") (pintype "passive"))
    )
    (net (code "135") (name "unconnected-(U1-VBAT-Pad1)") (class "Default")
      (node (ref "U1") (pin "1") (pinfunction "VBAT_1") (pintype "power_in"))
    )
    (net (code "136") (name "unconnected-(U8-R1IN-Pad13)") (class "Default")
      (node (ref "U8") (pin "13") (pinfunction "R1IN_13") (pintype "input"))
    )
    (net (code "137") (name "unconnected-(U8-R1OUT-Pad12)") (class "Default")
      (node (ref "U8") (pin "12") (pinfunction "R1OUT_12") (pintype "output"))
    )
    (net (code "138") (name "unconnected-(U8-T1IN-Pad11)") (class "Default")
      (node (ref "U8") (pin "11") (pinfunction "T1IN_11") (pintype "input"))
    )
    (net (code "139") (name "unconnected-(U8-T1OUT-Pad14)") (class "Default")
      (node (ref "U8") (pin "14") (pinfunction "T1OUT_14") (pintype "output"))
    )
    (net (code "140") (name "unconnected-(U9-IN6-Pad6)") (class "Default")
      (node (ref "U9") (pin "6") (pinfunction "IN6_6") (pintype "input"))
    )
    (net (code "141") (name "unconnected-(U9-IN7-Pad7)") (class "Default")
      (node (ref "U9") (pin "7") (pinfunction "IN7_7") (pintype "input"))
    )
    (net (code "142") (name "unconnected-(U9-OUT6-Pad11)") (class "Default")
      (node (ref "U9") (pin "11") (pinfunction "OUT6_11") (pintype "open_collector"))
    )
    (net (code "143") (name "unconnected-(U9-OUT7-Pad10)") (class "Default")
      (node (ref "U9") (pin "10") (pinfunction "OUT7_10") (pintype "open_collector"))
    )
    (net (code "144") (name "unconnected-(U15-ADC6-Pad19)") (class "Default")
      (node (ref "U15") (pin "19") (pinfunction "ADC6_19") (pintype "input"))
    )
    (net (code "145") (name "unconnected-(U15-ADC7-Pad22)") (class "Default")
      (node (ref "U15") (pin "22") (pinfunction "ADC7_22") (pintype "input"))
    )
    (net (code "146") (name "unconnected-(U15-AREF-Pad20)") (class "Default")
      (node (ref "U15") (pin "20") (pinfunction "AREF_20") (pintype "power_in"))
    )
    (net (code "147") (name "unconnected-(U15-PB1_(OC1A)-Pad13)") (class "Default")
      (node (ref "U15") (pin "13") (pinfunction "PB1_(OC1A)_13") (pintype "bidirectional"))
    )
  )
)
